# LoRa.net
KiCad netlist of a schematic drawn in Altium Designer
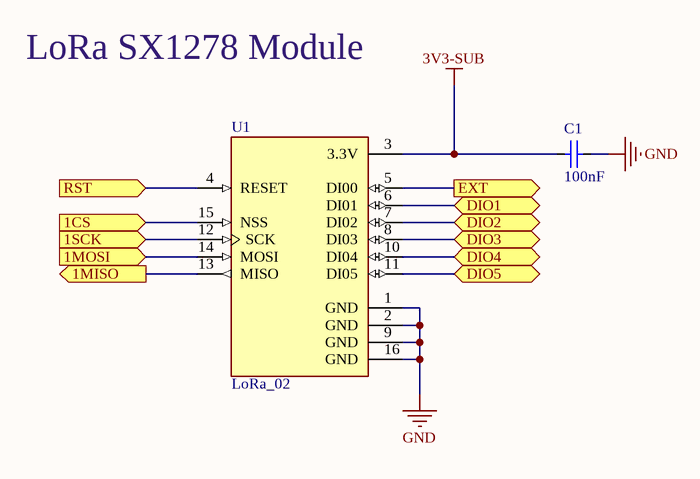
[diagram p0: LoRa.SchDoc]

(export (version "E")
  (design (tool "Eeschema 10.0.6"))
  (components
    (comp (ref "C1")
      (value "100nF")
      (footprint "CAP_0805")
      (description "Capacitor")
      (fields (field (name "PUBLISHER") "Altium Limited"))
      (libsource (lib "My Library") (part "CapSMD"))
    )
    (comp (ref "U1") (value "LoRa_02") (footprint "Ra-02") (libsource (lib "My Library") (part "LoRa_02")))
  )
  (nets
    (net (code "1") (name "/1CS") (class "Default")
      (node (ref "U1") (pin "15") (pinfunction "NSS_15") (pintype "input"))
    )
    (net (code "2") (name "/1MISO") (class "Default")
      (node (ref "U1") (pin "13") (pinfunction "MISO_13") (pintype "output"))
    )
    (net (code "3") (name "/1MOSI") (class "Default")
      (node (ref "U1") (pin "14") (pinfunction "MOSI_14") (pintype "input"))
    )
    (net (code "4") (name "/1SCK") (class "Default")
      (node (ref "U1") (pin "12") (pinfunction "SCK_12") (pintype "input"))
    )
    (net (code "5") (name "/DIO1") (class "Default")
      (node (ref "U1") (pin "6") (pinfunction "DI01_6") (pintype "bidirectional"))
    )
    (net (code "6") (name "/DIO2") (class "Default")
      (node (ref "U1") (pin "7") (pinfunction "DI02_7") (pintype "bidirectional"))
    )
    (net (code "7") (name "/DIO3") (class "Default")
      (node (ref "U1") (pin "8") (pinfunction "DI03_8") (pintype "bidirectional"))
    )
    (net (code "8") (name "/DIO4") (class "Default")
      (node (ref "U1") (pin "10") (pinfunction "DI04_10") (pintype "bidirectional"))
    )
    (net (code "9") (name "/DIO5") (class "Default")
      (node (ref "U1") (pin "11") (pinfunction "DI05_11") (pintype "bidirectional"))
    )
    (net (code "10") (name "/EXT") (class "Default")
      (node (ref "U1") (pin "5") (pinfunction "DI00_5") (pintype "bidirectional"))
    )
    (net (code "11") (name "/RST") (class "Default")
      (node (ref "U1") (pin "4") (pinfunction "RESET_4") (pintype "input"))
    )
    (net (code "12") (name "3V3-SUB") (class "Default")
      (node (ref "C1") (pin "1") (pinfunction "1_1") (pintype "passive"))
      (node (ref "U1") (pin "3") (pinfunction "3.3V_3") (pintype "power_in"))
    )
    (net (code "13") (name "GND") (class "Default")
      (node (ref "C1") (pin "2") (pinfunction "2_2") (pintype "passive"))
      (node (ref "U1") (pin "1") (pinfunction "GND_1") (pintype "power_in"))
      (node (ref "U1") (pin "16") (pinfunction "GND_16") (pintype "power_in"))
      (node (ref "U1") (pin "2") (pinfunction "GND_2") (pintype "power_in"))
      (node (ref "U1") (pin "9") (pinfunction "GND_9") (pintype "power_in"))
    )
  )
)
